# Control_board.net
KiCad netlist of a schematic drawn in EAGLE
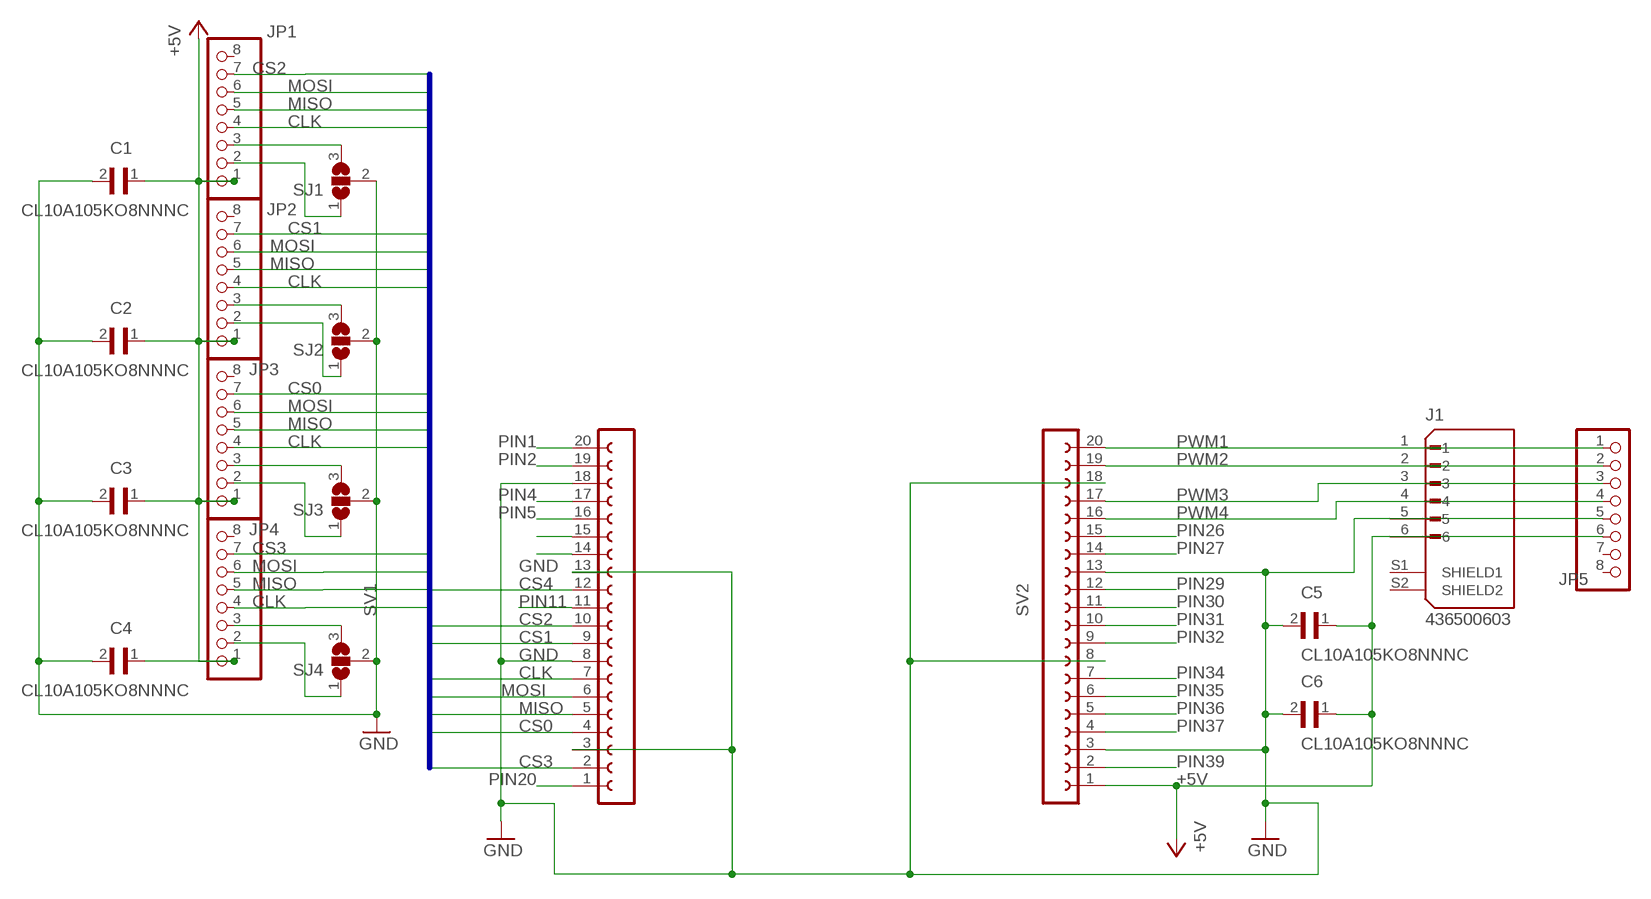
[diagram p0: schematic, sheet 1]

(export (version "E")
  (design (tool "Eeschema 10.0.6"))
  (components
    (comp (ref "C1")
      (value "CL10A105KO8NNNC")
      (footprint "eagle-import:CAPC1608X90N")
      (libsource (lib "eagle-import") (part "CL10A105KO8NNNC"))
    )
    (comp (ref "C2")
      (value "CL10A105KO8NNNC")
      (footprint "eagle-import:CAPC1608X90N")
      (libsource (lib "eagle-import") (part "CL10A105KO8NNNC"))
    )
    (comp (ref "C3")
      (value "CL10A105KO8NNNC")
      (footprint "eagle-import:CAPC1608X90N")
      (libsource (lib "eagle-import") (part "CL10A105KO8NNNC"))
    )
    (comp (ref "C4")
      (value "CL10A105KO8NNNC")
      (footprint "eagle-import:CAPC1608X90N")
      (libsource (lib "eagle-import") (part "CL10A105KO8NNNC"))
    )
    (comp (ref "C5")
      (value "CL10A105KO8NNNC")
      (footprint "eagle-import:CAPC1608X90N")
      (libsource (lib "eagle-import") (part "CL10A105KO8NNNC"))
    )
    (comp (ref "C6")
      (value "CL10A105KO8NNNC")
      (footprint "eagle-import:CAPC1608X90N")
      (libsource (lib "eagle-import") (part "CL10A105KO8NNNC"))
    )
    (comp (ref "J1")
      (value "436500603")
      (footprint "eagle-import:MOLEX_436500603")
      (fields (field (name "MANUFACTURER") "Molex"))
      (libsource (lib "eagle-import") (part "436500603"))
    )
    (comp (ref "JP1")
      (value "PINHD-1X81X08/FE")
      (footprint "eagle-import:HDRVR8W64P254_1X8_2159X200X810B")
      (libsource (lib "eagle-import") (part "PINHD-1X81X08/FE"))
    )
    (comp (ref "JP2")
      (value "PINHD-1X81X08/FE")
      (footprint "eagle-import:HDRVR8W64P254_1X8_2159X200X810B")
      (libsource (lib "eagle-import") (part "PINHD-1X81X08/FE"))
    )
    (comp (ref "JP3")
      (value "PINHD-1X81X08/FE")
      (footprint "eagle-import:HDRVR8W64P254_1X8_2159X200X810B")
      (libsource (lib "eagle-import") (part "PINHD-1X81X08/FE"))
    )
    (comp (ref "JP4")
      (value "PINHD-1X81X08/FE")
      (footprint "eagle-import:HDRVR8W64P254_1X8_2159X200X810B")
      (libsource (lib "eagle-import") (part "PINHD-1X81X08/FE"))
    )
    (comp (ref "JP5")
      (value "PINHD-1X81X08/FE")
      (footprint "eagle-import:HDRVR8W64P254_1X8_2159X200X810B")
      (libsource (lib "eagle-import") (part "PINHD-1X81X08/FE"))
    )
    (comp (ref "SJ1")
      (value "SJ2W")
      (footprint "eagle-import:SJ_2")
      (libsource (lib "eagle-import") (part "SJ2W"))
    )
    (comp (ref "SJ2")
      (value "SJ2W")
      (footprint "eagle-import:SJ_2")
      (libsource (lib "eagle-import") (part "SJ2W"))
    )
    (comp (ref "SJ3")
      (value "SJ2W")
      (footprint "eagle-import:SJ_2")
      (libsource (lib "eagle-import") (part "SJ2W"))
    )
    (comp (ref "SJ4")
      (value "SJ2W")
      (footprint "eagle-import:SJ_2")
      (libsource (lib "eagle-import") (part "SJ2W"))
    )
    (comp (ref "SV1")
      (value "FE20-1")
      (footprint "eagle-import:FE20")
      (libsource (lib "eagle-import") (part "FE20-1"))
    )
    (comp (ref "SV2")
      (value "FE20-1")
      (footprint "eagle-import:FE20")
      (libsource (lib "eagle-import") (part "FE20-1"))
    )
  )
  (nets
    (net (code "1") (name "+5V") (class "Default")
      (node (ref "C1") (pin "1") (pinfunction "1_1") (pintype "passive"))
      (node (ref "C2") (pin "1") (pinfunction "1_1") (pintype "passive"))
      (node (ref "C3") (pin "1") (pinfunction "1_1") (pintype "passive"))
      (node (ref "C4") (pin "1") (pinfunction "1_1") (pintype "passive"))
      (node (ref "C5") (pin "1") (pinfunction "1_1") (pintype "passive"))
      (node (ref "C6") (pin "1") (pinfunction "1_1") (pintype "passive"))
      (node (ref "J1") (pin "6") (pinfunction "6_6") (pintype "passive"))
      (node (ref "JP1") (pin "1") (pinfunction "1_1") (pintype "passive"))
      (node (ref "JP2") (pin "1") (pinfunction "1_1") (pintype "passive"))
      (node (ref "JP3") (pin "1") (pinfunction "1_1") (pintype "passive"))
      (node (ref "JP4") (pin "1") (pinfunction "1_1") (pintype "passive"))
      (node (ref "JP5") (pin "6") (pinfunction "6_6") (pintype "passive"))
      (node (ref "SV2") (pin "1") (pinfunction "1_1") (pintype "passive"))
    )
    (net (code "2") (name "/CLK") (class "Default")
      (node (ref "JP1") (pin "4") (pinfunction "4_4") (pintype "passive"))
      (node (ref "JP2") (pin "4") (pinfunction "4_4") (pintype "passive"))
      (node (ref "JP3") (pin "4") (pinfunction "4_4") (pintype "passive"))
      (node (ref "JP4") (pin "4") (pinfunction "4_4") (pintype "passive"))
      (node (ref "SV1") (pin "7") (pinfunction "7_7") (pintype "passive"))
    )
    (net (code "3") (name "/CS0") (class "Default")
      (node (ref "JP3") (pin "7") (pinfunction "7_7") (pintype "passive"))
      (node (ref "SV1") (pin "4") (pinfunction "4_4") (pintype "passive"))
    )
    (net (code "4") (name "/CS1") (class "Default")
      (node (ref "JP2") (pin "7") (pinfunction "7_7") (pintype "passive"))
      (node (ref "SV1") (pin "9") (pinfunction "9_9") (pintype "passive"))
    )
    (net (code "5") (name "/CS2") (class "Default")
      (node (ref "JP1") (pin "7") (pinfunction "7_7") (pintype "passive"))
      (node (ref "SV1") (pin "10") (pinfunction "10_10") (pintype "passive"))
    )
    (net (code "6") (name "/CS3") (class "Default")
      (node (ref "JP4") (pin "7") (pinfunction "7_7") (pintype "passive"))
      (node (ref "SV1") (pin "2") (pinfunction "2_2") (pintype "passive"))
    )
    (net (code "7") (name "/CS4") (class "Default")
      (node (ref "SV1") (pin "12") (pinfunction "12_12") (pintype "passive"))
    )
    (net (code "8") (name "/MISO") (class "Default")
      (node (ref "JP1") (pin "5") (pinfunction "5_5") (pintype "passive"))
      (node (ref "JP2") (pin "5") (pinfunction "5_5") (pintype "passive"))
      (node (ref "JP3") (pin "5") (pinfunction "5_5") (pintype "passive"))
      (node (ref "JP4") (pin "5") (pinfunction "5_5") (pintype "passive"))
      (node (ref "SV1") (pin "5") (pinfunction "5_5") (pintype "passive"))
    )
    (net (code "9") (name "/MOSI") (class "Default")
      (node (ref "JP1") (pin "6") (pinfunction "6_6") (pintype "passive"))
      (node (ref "JP2") (pin "6") (pinfunction "6_6") (pintype "passive"))
      (node (ref "JP3") (pin "6") (pinfunction "6_6") (pintype "passive"))
      (node (ref "JP4") (pin "6") (pinfunction "6_6") (pintype "passive"))
      (node (ref "SV1") (pin "6") (pinfunction "6_6") (pintype "passive"))
    )
    (net (code "10") (name "/PIN1") (class "Default")
      (node (ref "SV1") (pin "20") (pinfunction "20_20") (pintype "passive"))
    )
    (net (code "11") (name "/PIN2") (class "Default")
      (node (ref "SV1") (pin "19") (pinfunction "19_19") (pintype "passive"))
    )
    (net (code "12") (name "/PIN4") (class "Default")
      (node (ref "SV1") (pin "17") (pinfunction "17_17") (pintype "passive"))
    )
    (net (code "13") (name "/PIN5") (class "Default")
      (node (ref "SV1") (pin "16") (pinfunction "16_16") (pintype "passive"))
    )
    (net (code "14") (name "/PIN11") (class "Default")
      (node (ref "SV1") (pin "11") (pinfunction "11_11") (pintype "passive"))
    )
    (net (code "15") (name "/PIN20") (class "Default")
      (node (ref "SV1") (pin "1") (pinfunction "1_1") (pintype "passive"))
    )
    (net (code "16") (name "/PIN26") (class "Default")
      (node (ref "SV2") (pin "15") (pinfunction "15_15") (pintype "passive"))
    )
    (net (code "17") (name "/PIN27") (class "Default")
      (node (ref "SV2") (pin "14") (pinfunction "14_14") (pintype "passive"))
    )
    (net (code "18") (name "/PIN29") (class "Default")
      (node (ref "SV2") (pin "12") (pinfunction "12_12") (pintype "passive"))
    )
    (net (code "19") (name "/PIN30") (class "Default")
      (node (ref "SV2") (pin "11") (pinfunction "11_11") (pintype "passive"))
    )
    (net (code "20") (name "/PIN31") (class "Default")
      (node (ref "SV2") (pin "10") (pinfunction "10_10") (pintype "passive"))
    )
    (net (code "21") (name "/PIN32") (class "Default")
      (node (ref "SV2") (pin "9") (pinfunction "9_9") (pintype "passive"))
    )
    (net (code "22") (name "/PIN34") (class "Default")
      (node (ref "SV2") (pin "7") (pinfunction "7_7") (pintype "passive"))
    )
    (net (code "23") (name "/PIN35") (class "Default")
      (node (ref "SV2") (pin "6") (pinfunction "6_6") (pintype "passive"))
    )
    (net (code "24") (name "/PIN36") (class "Default")
      (node (ref "SV2") (pin "5") (pinfunction "5_5") (pintype "passive"))
    )
    (net (code "25") (name "/PIN37") (class "Default")
      (node (ref "SV2") (pin "4") (pinfunction "4_4") (pintype "passive"))
    )
    (net (code "26") (name "/PIN39") (class "Default")
      (node (ref "SV2") (pin "2") (pinfunction "2_2") (pintype "passive"))
    )
    (net (code "27") (name "/PWM1") (class "Default")
      (node (ref "J1") (pin "1") (pinfunction "1_1") (pintype "passive"))
      (node (ref "JP5") (pin "1") (pinfunction "1_1") (pintype "passive"))
      (node (ref "SV2") (pin "20") (pinfunction "20_20") (pintype "passive"))
    )
    (net (code "28") (name "/PWM2") (class "Default")
      (node (ref "J1") (pin "2") (pinfunction "2_2") (pintype "passive"))
      (node (ref "JP5") (pin "2") (pinfunction "2_2") (pintype "passive"))
      (node (ref "SV2") (pin "19") (pinfunction "19_19") (pintype "passive"))
    )
    (net (code "29") (name "/PWM3") (class "Default")
      (node (ref "J1") (pin "3") (pinfunction "3_3") (pintype "passive"))
      (node (ref "JP5") (pin "3") (pinfunction "3_3") (pintype "passive"))
      (node (ref "SV2") (pin "17") (pinfunction "17_17") (pintype "passive"))
    )
    (net (code "30") (name "/PWM4") (class "Default")
      (node (ref "J1") (pin "4") (pinfunction "4_4") (pintype "passive"))
      (node (ref "JP5") (pin "4") (pinfunction "4_4") (pintype "passive"))
      (node (ref "SV2") (pin "16") (pinfunction "16_16") (pintype "passive"))
    )
    (net (code "31") (name "GND") (class "Default")
      (node (ref "C1") (pin "2") (pinfunction "2_2") (pintype "passive"))
      (node (ref "C2") (pin "2") (pinfunction "2_2") (pintype "passive"))
      (node (ref "C3") (pin "2") (pinfunction "2_2") (pintype "passive"))
      (node (ref "C4") (pin "2") (pinfunction "2_2") (pintype "passive"))
      (node (ref "C5") (pin "2") (pinfunction "2_2") (pintype "passive"))
      (node (ref "C6") (pin "2") (pinfunction "2_2") (pintype "passive"))
      (node (ref "J1") (pin "5") (pinfunction "5_5") (pintype "passive"))
      (node (ref "JP5") (pin "5") (pinfunction "5_5") (pintype "passive"))
      (node (ref "SJ1") (pin "2") (pinfunction "2_2") (pintype "passive"))
      (node (ref "SJ2") (pin "2") (pinfunction "2_2") (pintype "passive"))
      (node (ref "SJ3") (pin "2") (pinfunction "2_2") (pintype "passive"))
      (node (ref "SJ4") (pin "2") (pinfunction "2_2") (pintype "passive"))
      (node (ref "SV1") (pin "13") (pinfunction "13_13") (pintype "passive"))
      (node (ref "SV1") (pin "18") (pinfunction "18_18") (pintype "passive"))
      (node (ref "SV1") (pin "3") (pinfunction "3_3") (pintype "passive"))
      (node (ref "SV1") (pin "8") (pinfunction "8_8") (pintype "passive"))
      (node (ref "SV2") (pin "13") (pinfunction "13_13") (pintype "passive"))
      (node (ref "SV2") (pin "18") (pinfunction "18_18") (pintype "passive"))
      (node (ref "SV2") (pin "3") (pinfunction "3_3") (pintype "passive"))
      (node (ref "SV2") (pin "8") (pinfunction "8_8") (pintype "passive"))
    )
    (net (code "32") (name "Net-(JP1-Pad2)") (class "Default")
      (node (ref "JP1") (pin "2") (pinfunction "2_2") (pintype "passive"))
      (node (ref "SJ1") (pin "1") (pinfunction "1_1") (pintype "passive"))
    )
    (net (code "33") (name "Net-(JP1-Pad3)") (class "Default")
      (node (ref "JP1") (pin "3") (pinfunction "3_3") (pintype "passive"))
      (node (ref "SJ1") (pin "3") (pinfunction "3_3") (pintype "passive"))
    )
    (net (code "34") (name "Net-(JP2-Pad2)") (class "Default")
      (node (ref "JP2") (pin "2") (pinfunction "2_2") (pintype "passive"))
      (node (ref "SJ2") (pin "1") (pinfunction "1_1") (pintype "passive"))
    )
    (net (code "35") (name "Net-(JP2-Pad3)") (class "Default")
      (node (ref "JP2") (pin "3") (pinfunction "3_3") (pintype "passive"))
      (node (ref "SJ2") (pin "3") (pinfunction "3_3") (pintype "passive"))
    )
    (net (code "36") (name "Net-(JP3-Pad2)") (class "Default")
      (node (ref "JP3") (pin "2") (pinfunction "2_2") (pintype "passive"))
      (node (ref "SJ3") (pin "1") (pinfunction "1_1") (pintype "passive"))
    )
    (net (code "37") (name "Net-(JP3-Pad3)") (class "Default")
      (node (ref "JP3") (pin "3") (pinfunction "3_3") (pintype "passive"))
      (node (ref "SJ3") (pin "3") (pinfunction "3_3") (pintype "passive"))
    )
    (net (code "38") (name "Net-(JP4-Pad2)") (class "Default")
      (node (ref "JP4") (pin "2") (pinfunction "2_2") (pintype "passive"))
      (node (ref "SJ4") (pin "1") (pinfunction "1_1") (pintype "passive"))
    )
    (net (code "39") (name "Net-(JP4-Pad3)") (class "Default")
      (node (ref "JP4") (pin "3") (pinfunction "3_3") (pintype "passive"))
      (node (ref "SJ4") (pin "3") (pinfunction "3_3") (pintype "passive"))
    )
    (net (code "40") (name "unconnected-(J1-SHIELD1-PadS1)") (class "Default")
      (node (ref "J1") (pin "S1") (pinfunction "SHIELD1_S1") (pintype "passive"))
    )
    (net (code "41") (name "unconnected-(J1-SHIELD2-PadS2)") (class "Default")
      (node (ref "J1") (pin "S2") (pinfunction "SHIELD2_S2") (pintype "passive"))
    )
    (net (code "42") (name "unconnected-(JP1-Pad8)") (class "Default")
      (node (ref "JP1") (pin "8") (pinfunction "8_8") (pintype "passive"))
    )
    (net (code "43") (name "unconnected-(JP2-Pad8)") (class "Default")
      (node (ref "JP2") (pin "8") (pinfunction "8_8") (pintype "passive"))
    )
    (net (code "44") (name "unconnected-(JP3-Pad8)") (class "Default")
      (node (ref "JP3") (pin "8") (pinfunction "8_8") (pintype "passive"))
    )
    (net (code "45") (name "unconnected-(JP4-Pad8)") (class "Default")
      (node (ref "JP4") (pin "8") (pinfunction "8_8") (pintype "passive"))
    )
    (net (code "46") (name "unconnected-(JP5-Pad7)") (class "Default")
      (node (ref "JP5") (pin "7") (pinfunction "7_7") (pintype "passive"))
    )
    (net (code "47") (name "unconnected-(JP5-Pad8)") (class "Default")
      (node (ref "JP5") (pin "8") (pinfunction "8_8") (pintype "passive"))
    )
    (net (code "48") (name "unconnected-(SV1-Pad14)") (class "Default")
      (node (ref "SV1") (pin "14") (pinfunction "14_14") (pintype "passive"))
    )
    (net (code "49") (name "unconnected-(SV1-Pad15)") (class "Default")
      (node (ref "SV1") (pin "15") (pinfunction "15_15") (pintype "passive"))
    )
  )
)
